# 4_sensores.net
KiCad netlist of a schematic drawn in Altium Designer
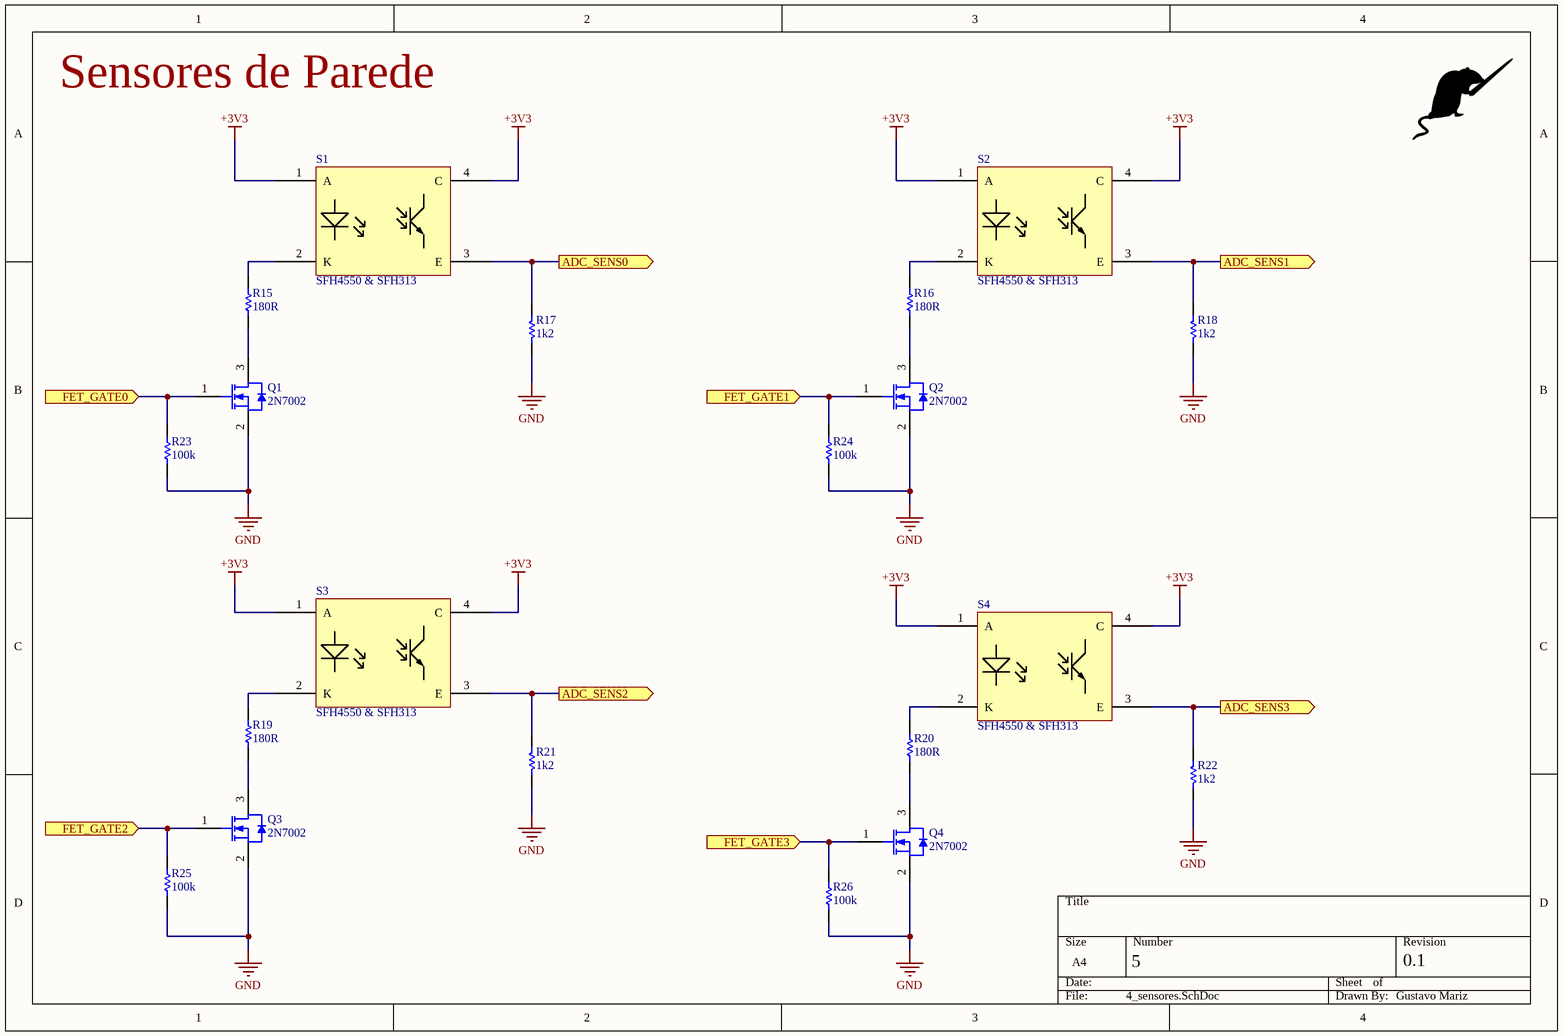
[diagram p0: 4_sensores.SchDoc]

(export (version "E")
  (design (tool "Eeschema 10.0.6"))
  (components
    (comp (ref "Q1")
      (value "2N7002")
      (footprint "STM-SOT-23-3_V")
      (description "N-channel 60 V, 1.8 Ohm, 0.35 A STripFET(TM) II Power MOSFET, SOT23")
      (fields (field (name "MANUFACTURER") "STMicroelectronics"))
      (libsource (lib "Altium Content Vault") (part "STM-NEMOS-G1S2D3-3"))
    )
    (comp (ref "Q2")
      (value "2N7002")
      (footprint "STM-SOT-23-3_V")
      (description "N-channel 60 V, 1.8 Ohm, 0.35 A STripFET(TM) II Power MOSFET, SOT23")
      (fields (field (name "MANUFACTURER") "STMicroelectronics"))
      (libsource (lib "Altium Content Vault") (part "STM-NEMOS-G1S2D3-3"))
    )
    (comp (ref "Q3")
      (value "2N7002")
      (footprint "STM-SOT-23-3_V")
      (description "N-channel 60 V, 1.8 Ohm, 0.35 A STripFET(TM) II Power MOSFET, SOT23")
      (fields (field (name "MANUFACTURER") "STMicroelectronics"))
      (libsource (lib "Altium Content Vault") (part "STM-NEMOS-G1S2D3-3"))
    )
    (comp (ref "Q4")
      (value "2N7002")
      (footprint "STM-SOT-23-3_V")
      (description "N-channel 60 V, 1.8 Ohm, 0.35 A STripFET(TM) II Power MOSFET, SOT23")
      (fields (field (name "MANUFACTURER") "STMicroelectronics"))
      (libsource (lib "Altium Content Vault") (part "STM-NEMOS-G1S2D3-3"))
    )
    (comp (ref "R15")
      (value "180R")
      (footprint "RES 0805")
      (description "Resistor")
      (fields (field (name "Comment") "RESISTOR"))
      (libsource (lib "Biblioteca Trincabotz (1)") (part "RESISTOR"))
    )
    (comp (ref "R16")
      (value "180R")
      (footprint "RES 0805")
      (description "Resistor")
      (fields (field (name "Comment") "RESISTOR"))
      (libsource (lib "Biblioteca Trincabotz (1)") (part "RESISTOR"))
    )
    (comp (ref "R17")
      (value "1k2")
      (footprint "RES 0805")
      (description "Resistor")
      (fields (field (name "Comment") "RESISTOR"))
      (libsource (lib "Biblioteca Trincabotz (1)") (part "RESISTOR"))
    )
    (comp (ref "R18")
      (value "1k2")
      (footprint "RES 0805")
      (description "Resistor")
      (fields (field (name "Comment") "RESISTOR"))
      (libsource (lib "Biblioteca Trincabotz (1)") (part "RESISTOR"))
    )
    (comp (ref "R19")
      (value "180R")
      (footprint "RES 0805")
      (description "Resistor")
      (fields (field (name "Comment") "RESISTOR"))
      (libsource (lib "Biblioteca Trincabotz (1)") (part "RESISTOR"))
    )
    (comp (ref "R20")
      (value "180R")
      (footprint "RES 0805")
      (description "Resistor")
      (fields (field (name "Comment") "RESISTOR"))
      (libsource (lib "Biblioteca Trincabotz (1)") (part "RESISTOR"))
    )
    (comp (ref "R21")
      (value "1k2")
      (footprint "RES 0805")
      (description "Resistor")
      (fields (field (name "Comment") "RESISTOR"))
      (libsource (lib "Biblioteca Trincabotz (1)") (part "RESISTOR"))
    )
    (comp (ref "R22")
      (value "1k2")
      (footprint "RES 0805")
      (description "Resistor")
      (fields (field (name "Comment") "RESISTOR"))
      (libsource (lib "Biblioteca Trincabotz (1)") (part "RESISTOR"))
    )
    (comp (ref "R23")
      (value "100k")
      (footprint "RES 0603")
      (description "Resistor")
      (fields (field (name "Comment") "RESISTOR"))
      (libsource (lib "Biblioteca Trincabotz (1)") (part "RESISTOR"))
    )
    (comp (ref "R24")
      (value "100k")
      (footprint "RES 0603")
      (description "Resistor")
      (fields (field (name "Comment") "RESISTOR"))
      (libsource (lib "Biblioteca Trincabotz (1)") (part "RESISTOR"))
    )
    (comp (ref "R25")
      (value "100k")
      (footprint "RES 0603")
      (description "Resistor")
      (fields (field (name "Comment") "RESISTOR"))
      (libsource (lib "Biblioteca Trincabotz (1)") (part "RESISTOR"))
    )
    (comp (ref "R26")
      (value "100k")
      (footprint "RES 0603")
      (description "Resistor")
      (fields (field (name "Comment") "RESISTOR"))
      (libsource (lib "Biblioteca Trincabotz (1)") (part "RESISTOR"))
    )
    (comp (ref "S1")
      (value "SFH4550 & SFH313")
      (footprint "umouse-sensor-fp")
      (libsource (lib "umouse-sensor") (part "SFH4550 & SFH313"))
    )
    (comp (ref "S2")
      (value "SFH4550 & SFH313")
      (footprint "umouse-sensor-fp")
      (libsource (lib "umouse-sensor") (part "SFH4550 & SFH313"))
    )
    (comp (ref "S3")
      (value "SFH4550 & SFH313")
      (footprint "umouse-sensor-fp")
      (libsource (lib "umouse-sensor") (part "SFH4550 & SFH313"))
    )
    (comp (ref "S4")
      (value "SFH4550 & SFH313")
      (footprint "umouse-sensor-fp")
      (libsource (lib "umouse-sensor") (part "SFH4550 & SFH313"))
    )
  )
  (nets
    (net (code "1") (name "+3V3") (class "Default")
      (node (ref "S1") (pin "1") (pinfunction "A_1") (pintype "passive"))
      (node (ref "S1") (pin "4") (pinfunction "C_4") (pintype "passive"))
      (node (ref "S2") (pin "1") (pinfunction "A_1") (pintype "passive"))
      (node (ref "S2") (pin "4") (pinfunction "C_4") (pintype "passive"))
      (node (ref "S3") (pin "1") (pinfunction "A_1") (pintype "passive"))
      (node (ref "S3") (pin "4") (pinfunction "C_4") (pintype "passive"))
      (node (ref "S4") (pin "1") (pinfunction "A_1") (pintype "passive"))
      (node (ref "S4") (pin "4") (pinfunction "C_4") (pintype "passive"))
    )
    (net (code "2") (name "/ADC_SENS0") (class "Default")
      (node (ref "R17") (pin "2") (pinfunction "2_2") (pintype "passive"))
      (node (ref "S1") (pin "3") (pinfunction "E_3") (pintype "passive"))
    )
    (net (code "3") (name "/ADC_SENS1") (class "Default")
      (node (ref "R18") (pin "2") (pinfunction "2_2") (pintype "passive"))
      (node (ref "S2") (pin "3") (pinfunction "E_3") (pintype "passive"))
    )
    (net (code "4") (name "/ADC_SENS2") (class "Default")
      (node (ref "R21") (pin "2") (pinfunction "2_2") (pintype "passive"))
      (node (ref "S3") (pin "3") (pinfunction "E_3") (pintype "passive"))
    )
    (net (code "5") (name "/ADC_SENS3") (class "Default")
      (node (ref "R22") (pin "2") (pinfunction "2_2") (pintype "passive"))
      (node (ref "S4") (pin "3") (pinfunction "E_3") (pintype "passive"))
    )
    (net (code "6") (name "/FET_GATE0") (class "Default")
      (node (ref "Q1") (pin "1") (pinfunction "G_1") (pintype "passive"))
      (node (ref "R23") (pin "2") (pinfunction "2_2") (pintype "passive"))
    )
    (net (code "7") (name "/FET_GATE1") (class "Default")
      (node (ref "Q2") (pin "1") (pinfunction "G_1") (pintype "passive"))
      (node (ref "R24") (pin "2") (pinfunction "2_2") (pintype "passive"))
    )
    (net (code "8") (name "/FET_GATE2") (class "Default")
      (node (ref "Q3") (pin "1") (pinfunction "G_1") (pintype "passive"))
      (node (ref "R25") (pin "2") (pinfunction "2_2") (pintype "passive"))
    )
    (net (code "9") (name "/FET_GATE3") (class "Default")
      (node (ref "Q4") (pin "1") (pinfunction "G_1") (pintype "passive"))
      (node (ref "R26") (pin "2") (pinfunction "2_2") (pintype "passive"))
    )
    (net (code "10") (name "GND") (class "Default")
      (node (ref "Q1") (pin "2") (pinfunction "S_2") (pintype "passive"))
      (node (ref "Q2") (pin "2") (pinfunction "S_2") (pintype "passive"))
      (node (ref "Q3") (pin "2") (pinfunction "S_2") (pintype "passive"))
      (node (ref "Q4") (pin "2") (pinfunction "S_2") (pintype "passive"))
      (node (ref "R17") (pin "1") (pinfunction "1_1") (pintype "passive"))
      (node (ref "R18") (pin "1") (pinfunction "1_1") (pintype "passive"))
      (node (ref "R21") (pin "1") (pinfunction "1_1") (pintype "passive"))
      (node (ref "R22") (pin "1") (pinfunction "1_1") (pintype "passive"))
      (node (ref "R23") (pin "1") (pinfunction "1_1") (pintype "passive"))
      (node (ref "R24") (pin "1") (pinfunction "1_1") (pintype "passive"))
      (node (ref "R25") (pin "1") (pinfunction "1_1") (pintype "passive"))
      (node (ref "R26") (pin "1") (pinfunction "1_1") (pintype "passive"))
    )
    (net (code "11") (name "Net-(Q1-D)") (class "Default")
      (node (ref "Q1") (pin "3") (pinfunction "D_3") (pintype "passive"))
      (node (ref "R15") (pin "1") (pinfunction "1_1") (pintype "passive"))
    )
    (net (code "12") (name "Net-(Q2-D)") (class "Default")
      (node (ref "Q2") (pin "3") (pinfunction "D_3") (pintype "passive"))
      (node (ref "R16") (pin "1") (pinfunction "1_1") (pintype "passive"))
    )
    (net (code "13") (name "Net-(Q3-D)") (class "Default")
      (node (ref "Q3") (pin "3") (pinfunction "D_3") (pintype "passive"))
      (node (ref "R19") (pin "1") (pinfunction "1_1") (pintype "passive"))
    )
    (net (code "14") (name "Net-(Q4-D)") (class "Default")
      (node (ref "Q4") (pin "3") (pinfunction "D_3") (pintype "passive"))
      (node (ref "R20") (pin "1") (pinfunction "1_1") (pintype "passive"))
    )
    (net (code "15") (name "Net-(S1-K)") (class "Default")
      (node (ref "R15") (pin "2") (pinfunction "2_2") (pintype "passive"))
      (node (ref "S1") (pin "2") (pinfunction "K_2") (pintype "passive"))
    )
    (net (code "16") (name "Net-(S2-K)") (class "Default")
      (node (ref "R16") (pin "2") (pinfunction "2_2") (pintype "passive"))
      (node (ref "S2") (pin "2") (pinfunction "K_2") (pintype "passive"))
    )
    (net (code "17") (name "Net-(S3-K)") (class "Default")
      (node (ref "R19") (pin "2") (pinfunction "2_2") (pintype "passive"))
      (node (ref "S3") (pin "2") (pinfunction "K_2") (pintype "passive"))
    )
    (net (code "18") (name "Net-(S4-K)") (class "Default")
      (node (ref "R20") (pin "2") (pinfunction "2_2") (pintype "passive"))
      (node (ref "S4") (pin "2") (pinfunction "K_2") (pintype "passive"))
    )
  )
)
